# BPW5038-MicroJoystick-Wing.net
KiCad netlist of a schematic drawn in EAGLE
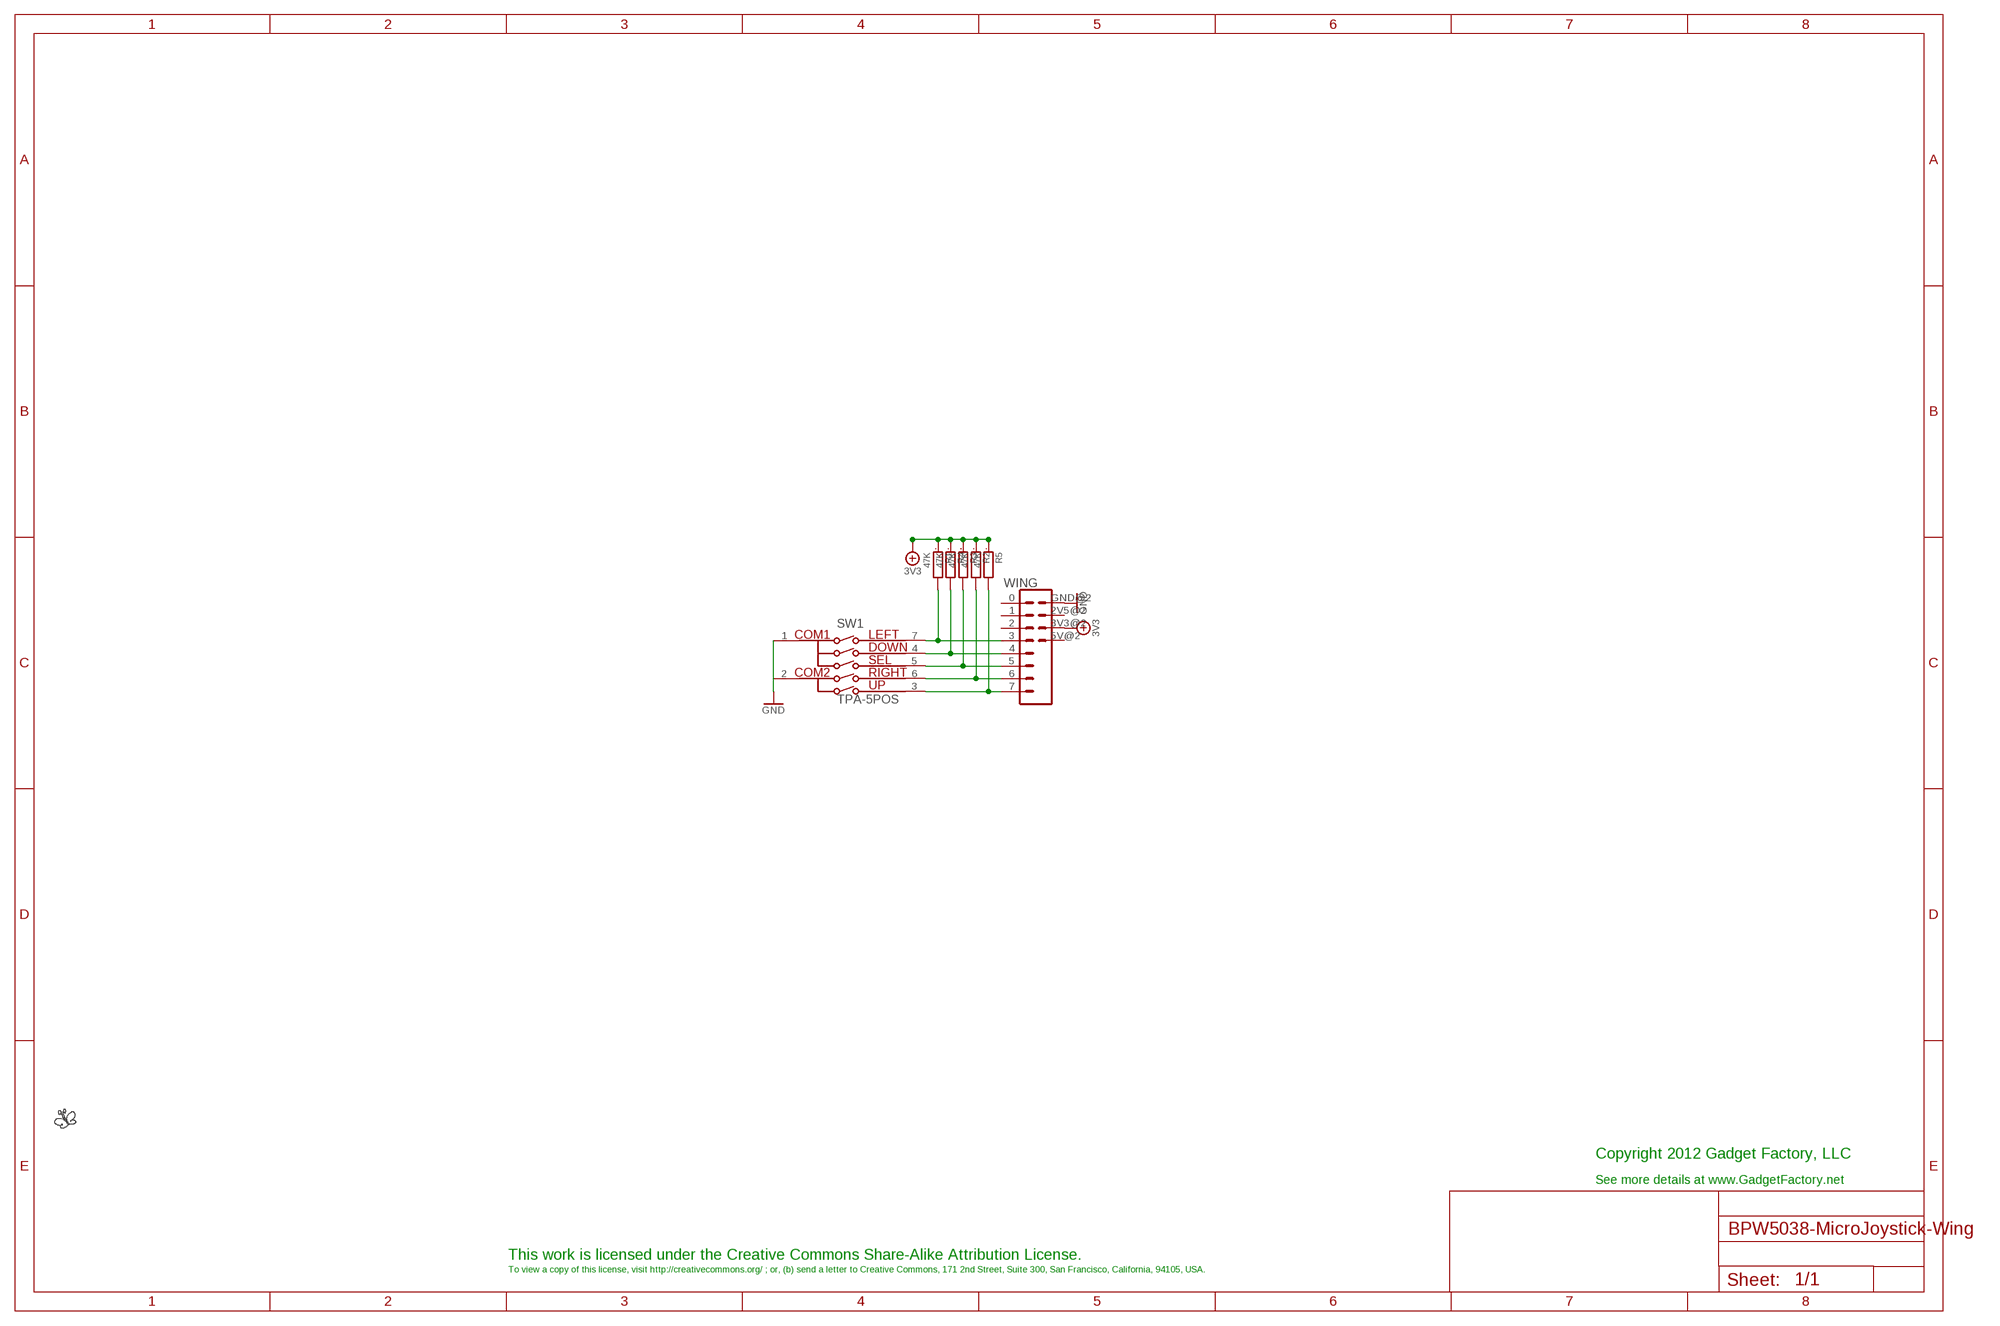
[diagram p0: schematic, sheet 1]

(export (version "E")
  (design (tool "Eeschema 10.0.6"))
  (components
    (comp (ref "LOGO1")
      (value "BUTTERFLY_LOGO")
      (footprint "eagle-import:BUTTERFLY_LOGO")
      (libsource (lib "eagle-import") (part "BUTTERFLY_LOGO"))
    )
    (comp (ref "R1")
      (value "47K")
      (footprint "eagle-import:0603")
      (libsource (lib "eagle-import") (part "R0603"))
    )
    (comp (ref "R2")
      (value "47K")
      (footprint "eagle-import:0603")
      (libsource (lib "eagle-import") (part "R0603"))
    )
    (comp (ref "R3")
      (value "47K")
      (footprint "eagle-import:0603")
      (libsource (lib "eagle-import") (part "R0603"))
    )
    (comp (ref "R4")
      (value "47K")
      (footprint "eagle-import:0603")
      (libsource (lib "eagle-import") (part "R0603"))
    )
    (comp (ref "R5")
      (value "47K")
      (footprint "eagle-import:0603")
      (libsource (lib "eagle-import") (part "R0603"))
    )
    (comp (ref "SW1")
      (value "TPA-5POS")
      (footprint "eagle-import:TPA-5POS")
      (libsource (lib "eagle-import") (part "TPA-5POS"))
    )
    (comp (ref "WING")
      (value "WING8")
      (footprint "eagle-import:WINGSIDE_8BIT")
      (libsource (lib "eagle-import") (part "WING8"))
    )
  )
  (nets
    (net (code "1") (name "3V3") (class "Default")
      (node (ref "R1") (pin "1") (pinfunction "1_1") (pintype "passive"))
      (node (ref "R2") (pin "1") (pinfunction "1_1") (pintype "passive"))
      (node (ref "R3") (pin "1") (pinfunction "1_1") (pintype "passive"))
      (node (ref "R4") (pin "1") (pinfunction "1_1") (pintype "passive"))
      (node (ref "R5") (pin "1") (pinfunction "1_1") (pintype "passive"))
      (node (ref "WING") (pin "3V3@2") (pinfunction "3V3_3V3@2") (pintype "passive"))
    )
    (net (code "2") (name "GND") (class "Default")
      (node (ref "SW1") (pin "1") (pinfunction "COM1_1") (pintype "passive"))
      (node (ref "SW1") (pin "2") (pinfunction "COM2_2") (pintype "passive"))
      (node (ref "WING") (pin "GND@2") (pinfunction "GND_GND@2") (pintype "passive"))
    )
    (net (code "3") (name "Net-(SW1-DOWN)") (class "Default")
      (node (ref "R4") (pin "2") (pinfunction "2_2") (pintype "passive"))
      (node (ref "SW1") (pin "4") (pinfunction "DOWN_4") (pintype "passive"))
      (node (ref "WING") (pin "4") (pinfunction "5_4") (pintype "passive"))
    )
    (net (code "4") (name "Net-(SW1-LEFT)") (class "Default")
      (node (ref "R1") (pin "2") (pinfunction "2_2") (pintype "passive"))
      (node (ref "SW1") (pin "7") (pinfunction "LEFT_7") (pintype "passive"))
      (node (ref "WING") (pin "3") (pinfunction "4_3") (pintype "passive"))
    )
    (net (code "5") (name "Net-(SW1-RIGHT)") (class "Default")
      (node (ref "R2") (pin "2") (pinfunction "2_2") (pintype "passive"))
      (node (ref "SW1") (pin "6") (pinfunction "RIGHT_6") (pintype "passive"))
      (node (ref "WING") (pin "6") (pinfunction "7_6") (pintype "passive"))
    )
    (net (code "6") (name "Net-(SW1-SELECT)") (class "Default")
      (node (ref "R3") (pin "2") (pinfunction "2_2") (pintype "passive"))
      (node (ref "SW1") (pin "5") (pinfunction "SELECT_5") (pintype "passive"))
      (node (ref "WING") (pin "5") (pinfunction "6_5") (pintype "passive"))
    )
    (net (code "7") (name "Net-(SW1-UP)") (class "Default")
      (node (ref "R5") (pin "2") (pinfunction "2_2") (pintype "passive"))
      (node (ref "SW1") (pin "3") (pinfunction "UP_3") (pintype "passive"))
      (node (ref "WING") (pin "7") (pinfunction "8_7") (pintype "passive"))
    )
    (net (code "8") (name "unconnected-(WING-1-Pad0)") (class "Default")
      (node (ref "WING") (pin "0") (pinfunction "1_0") (pintype "passive"))
    )
    (net (code "9") (name "unconnected-(WING-2-Pad1)") (class "Default")
      (node (ref "WING") (pin "1") (pinfunction "2_1") (pintype "passive"))
    )
    (net (code "10") (name "unconnected-(WING-2V5-Pad2V5@2)") (class "Default")
      (node (ref "WING") (pin "2V5@2") (pinfunction "2V5_2V5@2") (pintype "passive"))
    )
    (net (code "11") (name "unconnected-(WING-3-Pad2)") (class "Default")
      (node (ref "WING") (pin "2") (pinfunction "3_2") (pintype "passive"))
    )
    (net (code "12") (name "unconnected-(WING-5V-Pad5V@2)") (class "Default")
      (node (ref "WING") (pin "5V@2") (pinfunction "5V_5V@2") (pintype "passive"))
    )
  )
)
